# 12V_Buck.net
KiCad netlist of a schematic drawn in Altium Designer
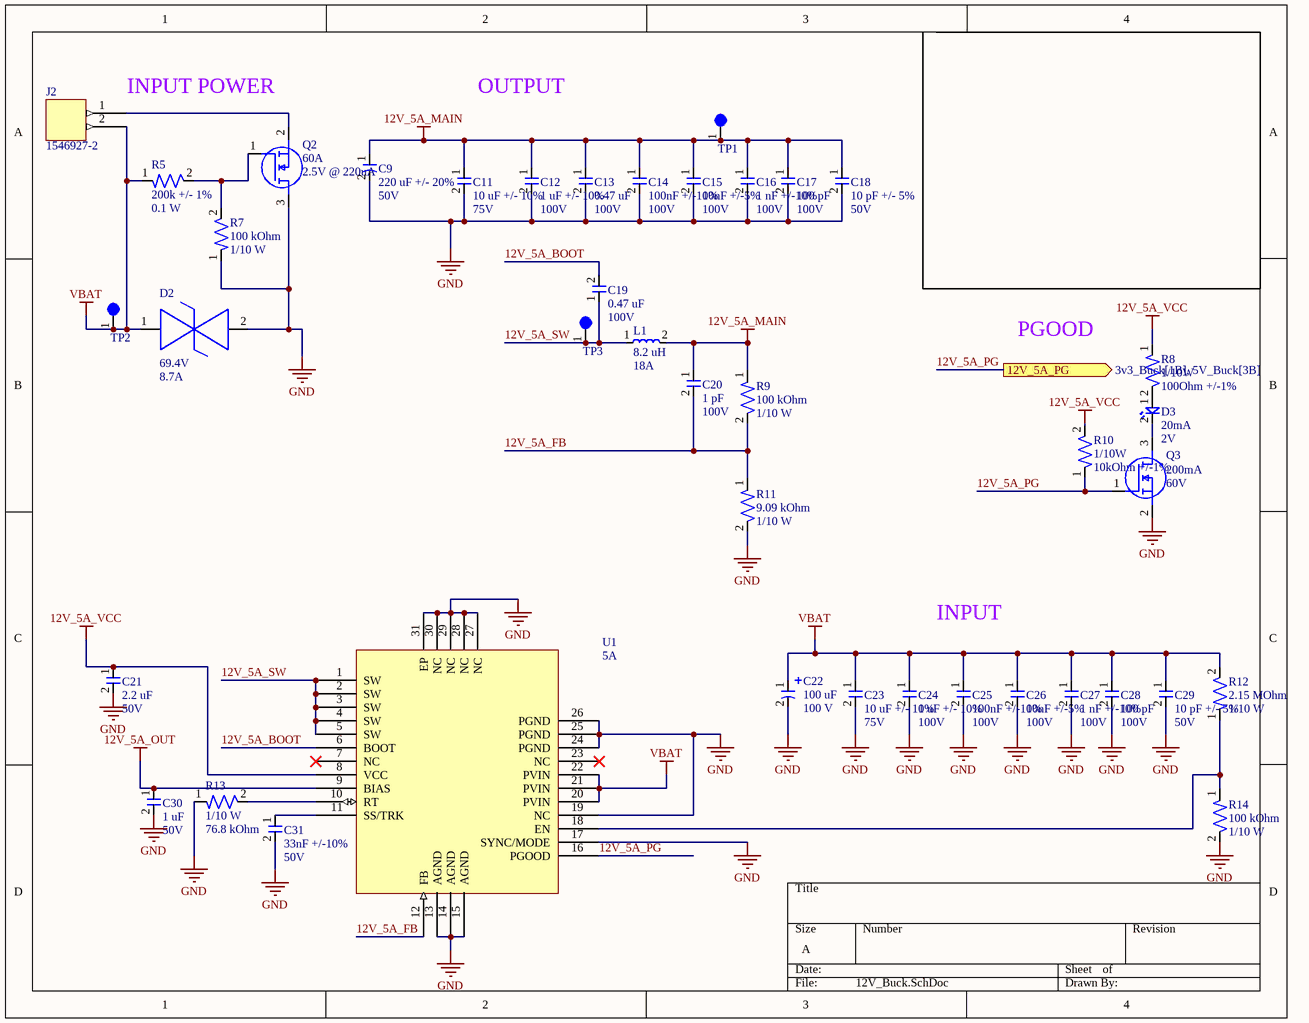
[diagram p0: 12V_Buck.SchDoc]

(export (version "E")
  (design (tool "Eeschema 10.0.6"))
  (components
    (comp (ref "C9")
      (value "50TZV220M10X10.5")
      (footprint "ELEC-220U-0003")
      (description "220 µF 50 V Aluminum Electrolytic Capacitors Radial, Can - SMD 2000 Hrs @ 105°C")
      (fields (field (name "CAPACITANCE") "220 uF +/- 20%") (field (name "VOLTAGE RATING") "50V"))
      (libsource (lib "MasterLib") (part "ELEC-220U-0003"))
    )
    (comp (ref "C11")
      (value "C3225X7R1N106K250AC")
      (footprint "CAP-1210")
      (description "10 µF ±10% 75V Ceramic Capacitor X7R 1210 (3225 Metric)")
      (fields (field (name "CAPACITANCE") "10 uF +/- 10%") (field (name "VOLTAGE RATING") "75V"))
      (libsource (lib "MasterLib") (part "CAP-10U-0004"))
    )
    (comp (ref "C12")
      (value "CL31B105KCHNNNE")
      (footprint "CAP-1206 - duplicate")
      (description "1 µF ±10% 100V Ceramic Capacitor X7R 1206 (3216 Metric)")
      (fields (field (name "CAPACITANCE") "1 uF +/- 10%") (field (name "VOLTAGE") "100V"))
      (libsource (lib "MasterLib") (part "CAP-1U-0001"))
    )
    (comp (ref "C13")
      (value "KAM21KR72A474KL")
      (footprint "CAP-0805")
      (description "0.47 µF ±10% 100V Ceramic Capacitor X7R 0805 (2012 Metric)")
      (fields
        (field (name "TOLERANCE") "+/- 10%")
        (field (name "CAPACITANCE") "0.47 uF")
        (field (name "VOLTAGE") "100V")
      )
      (libsource (lib "MasterLib") (part "CAP-0.47U-0001"))
    )
    (comp (ref "C14")
      (value "CC0603KRX7R0BB104")
      (footprint "CAP-0603")
      (description "CAP CER 0.1UF 100V X7R 0603")
      (fields
        (field (name "MANUFACTURER") "YAGEO")
        (field (name "CAPACITANCE") "100nF +/-10%")
        (field (name "VOLTAGE RATING") "100V")
      )
      (libsource (lib "MasterLib") (part "CAP-100N-0001"))
    )
    (comp (ref "C15")
      (value "C1608C0G2A103J080AC")
      (footprint "CAP-0603")
      (description "CAP CER 10000PF 100V C0G 0603")
      (fields
        (field (name "MANUFACTURER") "TDK Corporation")
        (field (name "CAPACITANCE") "10nF +/-5%")
        (field (name "VOLTAGE RATING") "100V")
      )
      (libsource (lib "MasterLib") (part "CAP-10N-0002"))
    )
    (comp (ref "C16")
      (value "C0603Y102K1RAC7867")
      (footprint "CAP-0603")
      (description "1000 pF ±10% 100V Ceramic Capacitor X7R 0603 (1608 Metric)")
      (fields (field (name "CAPACITANCE") "1 nF +/-10%") (field (name "VOLTAGE") "100V"))
      (libsource (lib "MasterLib") (part "CAP-1N-0001"))
    )
    (comp (ref "C17")
      (value "0603N101J101CT")
      (footprint "CAP-0603")
      (description "100 pF ±5% 100V Ceramic Capacitor C0G, NP0 0603 (1608 Metric)")
      (fields
        (field (name "TOLERANCE") "+/-5%")
        (field (name "CAPACITANCE") "100 pF")
        (field (name "VOLTAGE") "100V")
      )
      (libsource (lib "MasterLib") (part "CAP-100P-0002"))
    )
    (comp (ref "C18")
      (value "0603N100J500CT")
      (footprint "CAP-0603")
      (description "10 pF ±5% 50V Ceramic Capacitor C0G, NP0 0603 (1608 Metric)")
      (fields
        (field (name "MANUFACTURER") "Walshin Technology Corporation")
        (field (name "CAPACITANCE") "10 pF +/- 5%")
        (field (name "VOLTAGE RATING") "50V")
      )
      (libsource (lib "MasterLib") (part "CAP-10P-0001"))
    )
    (comp (ref "C19")
      (value "KAM21KR72A474KL")
      (footprint "CAP-0805")
      (description "0.47 µF ±10% 100V Ceramic Capacitor X7R 0805 (2012 Metric)")
      (fields
        (field (name "TOLERANCE") "+/- 10%")
        (field (name "CAPACITANCE") "0.47 uF")
        (field (name "VOLTAGE") "100V")
      )
      (libsource (lib "MasterLib") (part "CAP-0.47U-0001"))
    )
    (comp (ref "C20")
      (value "885012006087")
      (footprint "CAP-0603")
      (description "1 pF ±0.25pF 100V Ceramic Capacitor C0G, NP0 0603 (1608 Metric)")
      (fields
        (field (name "TOLERANCE") "+/- 0.25 pF")
        (field (name "CAPACITANCE") "1 pF")
        (field (name "VOLTAGE") "100V")
      )
      (libsource (lib "MasterLib") (part "CAP-1P-0001"))
    )
    (comp (ref "C21")
      (value "UMK107BBJ225KA-T")
      (footprint "CAP-0603")
      (description "2.2 µF ±10% 50V Ceramic Capacitor X5R 0603 (1608 Metric)")
      (fields (field (name "CAPACITANCE") "2.2 uF") (field (name "OLTAGE") "50V"))
      (libsource (lib "MasterLib") (part "CAP-2.2U-0001"))
    )
    (comp (ref "C22")
      (value "100SEV100M12.5X16")
      (footprint "ELEC-100U-0001")
      (description "100 µF 100 V Aluminum Electrolytic Capacitors Radial, Can - SMD 2000 Hrs @ 85°C")
      (fields
        (field (name "MANUFACTURER") "Rubycon")
        (field (name "TOLERANCE") "+/- 20%")
        (field (name "CAPACITANCE") "100 uF")
        (field (name "VOLTAGE") "100 V")
      )
      (libsource (lib "MasterLib") (part "ELEC-100U-0001"))
    )
    (comp (ref "C23")
      (value "C3225X7R1N106K250AC")
      (footprint "CAP-1210")
      (description "10 µF ±10% 75V Ceramic Capacitor X7R 1210 (3225 Metric)")
      (fields (field (name "CAPACITANCE") "10 uF +/- 10%") (field (name "VOLTAGE RATING") "75V"))
      (libsource (lib "MasterLib") (part "CAP-10U-0004"))
    )
    (comp (ref "C24")
      (value "CL31B105KCHNNNE")
      (footprint "CAP-1206 - duplicate")
      (description "1 µF ±10% 100V Ceramic Capacitor X7R 1206 (3216 Metric)")
      (fields (field (name "CAPACITANCE") "1 uF +/- 10%") (field (name "VOLTAGE") "100V"))
      (libsource (lib "MasterLib") (part "CAP-1U-0001"))
    )
    (comp (ref "C25")
      (value "CC0603KRX7R0BB104")
      (footprint "CAP-0603")
      (description "CAP CER 0.1UF 100V X7R 0603")
      (fields
        (field (name "MANUFACTURER") "YAGEO")
        (field (name "CAPACITANCE") "100nF +/-10%")
        (field (name "VOLTAGE RATING") "100V")
      )
      (libsource (lib "MasterLib") (part "CAP-100N-0001"))
    )
    (comp (ref "C26")
      (value "C1608C0G2A103J080AC")
      (footprint "CAP-0603")
      (description "CAP CER 10000PF 100V C0G 0603")
      (fields
        (field (name "MANUFACTURER") "TDK Corporation")
        (field (name "CAPACITANCE") "10nF +/-5%")
        (field (name "VOLTAGE RATING") "100V")
      )
      (libsource (lib "MasterLib") (part "CAP-10N-0002"))
    )
    (comp (ref "C27")
      (value "C0603Y102K1RAC7867")
      (footprint "CAP-0603")
      (description "1000 pF ±10% 100V Ceramic Capacitor X7R 0603 (1608 Metric)")
      (fields (field (name "CAPACITANCE") "1 nF +/-10%") (field (name "VOLTAGE") "100V"))
      (libsource (lib "MasterLib") (part "CAP-1N-0001"))
    )
    (comp (ref "C28")
      (value "0603N101J101CT")
      (footprint "CAP-0603")
      (description "100 pF ±5% 100V Ceramic Capacitor C0G, NP0 0603 (1608 Metric)")
      (fields
        (field (name "TOLERANCE") "+/-5%")
        (field (name "CAPACITANCE") "100 pF")
        (field (name "VOLTAGE") "100V")
      )
      (libsource (lib "MasterLib") (part "CAP-100P-0002"))
    )
    (comp (ref "C29")
      (value "0603N100J500CT")
      (footprint "CAP-0603")
      (description "10 pF ±5% 50V Ceramic Capacitor C0G, NP0 0603 (1608 Metric)")
      (fields
        (field (name "MANUFACTURER") "Walshin Technology Corporation")
        (field (name "CAPACITANCE") "10 pF +/- 5%")
        (field (name "VOLTAGE RATING") "50V")
      )
      (libsource (lib "MasterLib") (part "CAP-10P-0001"))
    )
    (comp (ref "C30")
      (value "UMK107AB7105KA-T")
      (footprint "CAP-0603")
      (description "1 µF ±10% 50V Ceramic Capacitor X7R 0603 (1608 Metric)")
      (fields (field (name "CAPACITANCE") "1 uF") (field (name "VOLTAGE") "50V"))
      (libsource (lib "MasterLib") (part "CAP-1U-0002"))
    )
    (comp (ref "C31")
      (value "CC0603KRX7R9BB333")
      (footprint "CAP-0603")
      (description "0.033 µF ±10% 50V Ceramic Capacitor X7R 0603 (1608 Metric)")
      (fields
        (field (name "MANUFACTURER") "YAGEO")
        (field (name "CAPACITANCE") "33nF +/-10%")
        (field (name "VOLTAGE RATING") "50V")
      )
      (libsource (lib "MasterLib") (part "CAP-33N-0001"))
    )
    (comp (ref "D2")
      (value "SMBJE43CAH")
      (footprint "DO-214AA (SMBJ)")
      (description "69.4V Clamp 8.7A Ipp Tvs Diode Surface Mount DO-214AA (SMBJ)")
      (fields (field (name "VCLAMP") "69.4V") (field (name "PEAK PULSER CURRENT") "8.7A"))
      (libsource (lib "MasterLib") (part "DIO-69.4V-0001"))
    )
    (comp (ref "D3")
      (value "150060AS75000")
      (footprint "LED-0603")
      (description "CAP CER 0.1UF 100V X7R 0603")
      (fields
        (field (name "MANUFACTURER") "Wurth Electronik")
        (field (name "CURRENT RATING") "20mA")
        (field (name "VF") "2V")
      )
      (libsource (lib "MasterLib") (part "LED_Amber_0001"))
    )
    (comp (ref "J2")
      (value "1546927-2")
      (footprint "CONN-1546927-2")
      (libsource (lib "MasterLib") (part "CON-2POS-0003"))
    )
    (comp (ref "L1")
      (value "IHLP6767GZER8R2M01")
      (footprint "PWRIND-8.2U-0002")
      (description "8.2 µH Shielded Molded Inductor 18 A 10.66mOhm Max Nonstandard")
      (fields
        (field (name "TOLERANCE") "+/-20%")
        (field (name "INDUCTANCE") "8.2 uH")
        (field (name "DCI") "18A")
      )
      (libsource (lib "MasterLib") (part "PWRIND-8.2U-0002"))
    )
    (comp (ref "Q2")
      (value "TPH7R006PL,L1Q")
      (footprint "NMOS-8PowerVDFN")
      (description "N-Channel 60 V 60A (Tc) 81W (Tc) Surface Mount 8-SOP Advance (5x5)")
      (fields (field (name "DRAIN CURRENT") "60A") (field (name "VGS") "2.5V @ 220uA"))
      (libsource (lib "MasterLib") (part "NMOS-60A-0001"))
    )
    (comp (ref "Q3")
      (value "T2N7002AK,LM")
      (footprint "NMOS-SOT23-3")
      (description "MOSFET N-CH 60V 200MA SOT23")
      (fields
        (field (name "MANUFACTURER") "Toshiba")
        (field (name "ID-CONTINUOUS") "200mA")
        (field (name "VDS-MAX") "60V")
      )
      (libsource (lib "MasterLib") (part "NMOS-200MA-0001"))
    )
    (comp (ref "R5")
      (value "ERJ-3EKF2003V")
      (footprint "RES-0603")
      (description "200 kOhms ±1% 0.1W, 1/10W Chip Resistor 0603 (1608 Metric) Automotive AEC-Q200 Thick Film")
      (fields
        (field (name "MANUFACTURER") "Panasonic Electronic Components")
        (field (name "RESISTANCE") "200k +/- 1%")
        (field (name "POWER RATING") "0.1 W")
      )
      (libsource (lib "MasterLib") (part "RES-200K-0001"))
    )
    (comp (ref "R7")
      (value "RC0603FR-07100KL")
      (footprint "RES-0603")
      (description "100 kOhms ±1% 0.1W, 1/10W Chip Resistor 0603 (1608 Metric) Moisture Resistant Thick Film")
      (fields
        (field (name "TOLERANCE") "+/- 1%")
        (field (name "RESISTANCE") "100 kOhm")
        (field (name "POWER") "1/10 W")
      )
      (libsource (lib "MasterLib") (part "RES-100K-0003"))
    )
    (comp (ref "R8")
      (value "AC0603FR-10100RL")
      (footprint "RES-0603")
      (description "100 Ohms ±1% 0.1W, 1/10W Chip Resistor 0603 (1608 Metric) Automotive AEC-Q200 Thick Film")
      (fields
        (field (name "MANUFACTURER") "YAGEO")
        (field (name "POWER RATING") "1/10W")
        (field (name "RESISTANCE") "100Ohm +/-1%")
      )
      (libsource (lib "MasterLib") (part "RES-100-0002"))
    )
    (comp (ref "R9")
      (value "RC0603FR-07100KL")
      (footprint "RES-0603")
      (description "100 kOhms ±1% 0.1W, 1/10W Chip Resistor 0603 (1608 Metric) Moisture Resistant Thick Film")
      (fields
        (field (name "TOLERANCE") "+/- 1%")
        (field (name "RESISTANCE") "100 kOhm")
        (field (name "POWER") "1/10 W")
      )
      (libsource (lib "MasterLib") (part "RES-100K-0003"))
    )
    (comp (ref "R10")
      (value "RC0603FR-0710KP")
      (footprint "RES-0603")
      (description "RES SMD 10K OHM 1% 1/10W 0603")
      (fields
        (field (name "MANUFACTURER") "YAGEO")
        (field (name "POWER RATING") "1/10W")
        (field (name "RESISTANCE") "10kOhm +/-1%")
      )
      (libsource (lib "MasterLib") (part "RES-10K-0002"))
    )
    (comp (ref "R11")
      (value "RC0603FR-079K09L")
      (footprint "RES-0603")
      (description "9.09 kOhms ±1% 0.1W, 1/10W Chip Resistor 0603 (1608 Metric) Moisture Resistant Thick Film")
      (fields
        (field (name "TOLERANCE") "+/-1%")
        (field (name "RESISTANCE") "9.09 kOhm")
        (field (name "POWER") "1/10 W")
      )
      (libsource (lib "MasterLib") (part "RES-9.09K-0001"))
    )
    (comp (ref "R12")
      (value "RC0603FR-072M15L")
      (footprint "RES-0603")
      (description "2.15 MOhms ±1% 0.1W, 1/10W Chip Resistor 0603 (1608 Metric) Moisture Resistant Thick Film")
      (fields
        (field (name "TOLERANCE") "+/-1%")
        (field (name "RESISTANCE") "2.15 MOhm")
        (field (name "POWER") "1/10 W")
      )
      (libsource (lib "MasterLib") (part "RES-2.15M-0001"))
    )
    (comp (ref "R13")
      (value "RC0603FR-0776K8L")
      (footprint "RES-0603")
      (description "76.8 kOhms ±1% 0.1W, 1/10W Chip Resistor 0603 (1608 Metric) Moisture Resistant Thick Film")
      (fields
        (field (name "MANUFACTURER") "Yageo")
        (field (name "TOLERANCE") "+/- 1%")
        (field (name "POWER") "1/10 W")
        (field (name "RESISTANCE") "76.8 kOhm")
      )
      (libsource (lib "MasterLib") (part "RES-76.8K-0001"))
    )
    (comp (ref "R14")
      (value "RC0603FR-07100KL")
      (footprint "RES-0603")
      (description "100 kOhms ±1% 0.1W, 1/10W Chip Resistor 0603 (1608 Metric) Moisture Resistant Thick Film")
      (fields
        (field (name "TOLERANCE") "+/- 1%")
        (field (name "RESISTANCE") "100 kOhm")
        (field (name "POWER") "1/10 W")
      )
      (libsource (lib "MasterLib") (part "RES-100K-0003"))
    )
    (comp (ref "TP1")
      (value "5003")
      (footprint "TEST-POINT-0001")
      (description "Oranange PC Test Point, Miniature Phoisphor Bronze Silver Plating Through Hole Mounting Type")
      (libsource (lib "MasterLib") (part "TEST-POINT-0001"))
    )
    (comp (ref "TP2")
      (value "5003")
      (footprint "TEST-POINT-0001")
      (description "Oranange PC Test Point, Miniature Phoisphor Bronze Silver Plating Through Hole Mounting Type")
      (libsource (lib "MasterLib") (part "TEST-POINT-0001"))
    )
    (comp (ref "TP3")
      (value "5003")
      (footprint "TEST-POINT-0001")
      (description "Oranange PC Test Point, Miniature Phoisphor Bronze Silver Plating Through Hole Mounting Type")
      (libsource (lib "MasterLib") (part "TEST-POINT-0001"))
    )
    (comp (ref "U1")
      (value "LM76005RNPR")
      (footprint "IC-30-WQFN(6x4)")
      (description "Buck Switching Regulator IC Positive Adjustable 1V 1 Output 5A 30-WFQFN Exposed Pad")
      (fields (field (name "MANUFACTURER") "Texas Instruments") (field (name "CURRENT") "5A"))
      (libsource (lib "MasterLib") (part "IC-BUCK-0006"))
    )
  )
  (nets
    (net (code "1") (name "/12V_5A_BOOT") (class "Default")
      (node (ref "C19") (pin "2") (pinfunction "2_2") (pintype "passive"))
      (node (ref "U1") (pin "6") (pinfunction "BOOT_6") (pintype "power_in"))
    )
    (net (code "2") (name "/12V_5A_FB") (class "Default")
      (node (ref "C20") (pin "2") (pinfunction "2_2") (pintype "passive"))
      (node (ref "R11") (pin "1") (pinfunction "1_1") (pintype "passive"))
      (node (ref "R9") (pin "2") (pinfunction "2_2") (pintype "passive"))
      (node (ref "U1") (pin "12") (pinfunction "FB_12") (pintype "input"))
    )
    (net (code "3") (name "/12V_5A_PG") (class "Default")
      (node (ref "Q3") (pin "1") (pinfunction "G_1") (pintype "passive"))
      (node (ref "R10") (pin "1") (pinfunction "1_1") (pintype "passive"))
      (node (ref "U1") (pin "16") (pinfunction "PGOOD_16") (pintype "power_in"))
    )
    (net (code "4") (name "/12V_5A_SW") (class "Default")
      (node (ref "C19") (pin "1") (pinfunction "1_1") (pintype "passive"))
      (node (ref "L1") (pin "1") (pinfunction "1_1") (pintype "passive"))
      (node (ref "TP3") (pin "1") (pinfunction "0_1") (pintype "passive"))
      (node (ref "U1") (pin "1") (pinfunction "SW_1") (pintype "power_in"))
      (node (ref "U1") (pin "2") (pinfunction "SW_2") (pintype "power_in"))
      (node (ref "U1") (pin "3") (pinfunction "SW_3") (pintype "power_in"))
      (node (ref "U1") (pin "4") (pinfunction "SW_4") (pintype "power_in"))
      (node (ref "U1") (pin "5") (pinfunction "SW_5") (pintype "power_in"))
    )
    (net (code "5") (name "12V_5A_MAIN") (class "Default")
      (node (ref "C11") (pin "1") (pinfunction "1_1") (pintype "passive"))
      (node (ref "C12") (pin "1") (pinfunction "1_1") (pintype "passive"))
      (node (ref "C13") (pin "1") (pinfunction "1_1") (pintype "passive"))
      (node (ref "C14") (pin "1") (pinfunction "1_1") (pintype "passive"))
      (node (ref "C15") (pin "1") (pinfunction "1_1") (pintype "passive"))
      (node (ref "C16") (pin "1") (pinfunction "1_1") (pintype "passive"))
      (node (ref "C17") (pin "1") (pinfunction "1_1") (pintype "passive"))
      (node (ref "C18") (pin "1") (pinfunction "1_1") (pintype "passive"))
      (node (ref "C20") (pin "1") (pinfunction "1_1") (pintype "passive"))
      (node (ref "C9") (pin "1") (pinfunction "1_1") (pintype "passive"))
      (node (ref "L1") (pin "2") (pinfunction "2_2") (pintype "passive"))
      (node (ref "R9") (pin "1") (pinfunction "1_1") (pintype "passive"))
      (node (ref "TP1") (pin "1") (pinfunction "0_1") (pintype "passive"))
    )
    (net (code "6") (name "12V_5A_OUT") (class "Default")
      (node (ref "C30") (pin "1") (pinfunction "1_1") (pintype "passive"))
      (node (ref "U1") (pin "9") (pinfunction "BIAS_9") (pintype "power_in"))
    )
    (net (code "7") (name "12V_5A_VCC") (class "Default")
      (node (ref "C21") (pin "1") (pinfunction "1_1") (pintype "passive"))
      (node (ref "R10") (pin "2") (pinfunction "2_2") (pintype "passive"))
      (node (ref "R8") (pin "1") (pinfunction "1_1") (pintype "passive"))
      (node (ref "U1") (pin "8") (pinfunction "VCC_8") (pintype "power_in"))
    )
    (net (code "8") (name "GND") (class "Default")
      (node (ref "C11") (pin "2") (pinfunction "2_2") (pintype "passive"))
      (node (ref "C12") (pin "2") (pinfunction "2_2") (pintype "passive"))
      (node (ref "C13") (pin "2") (pinfunction "2_2") (pintype "passive"))
      (node (ref "C14") (pin "2") (pinfunction "2_2") (pintype "passive"))
      (node (ref "C15") (pin "2") (pinfunction "2_2") (pintype "passive"))
      (node (ref "C16") (pin "2") (pinfunction "2_2") (pintype "passive"))
      (node (ref "C17") (pin "2") (pinfunction "2_2") (pintype "passive"))
      (node (ref "C18") (pin "2") (pinfunction "2_2") (pintype "passive"))
      (node (ref "C21") (pin "2") (pinfunction "2_2") (pintype "passive"))
      (node (ref "C22") (pin "2") (pinfunction "2_2") (pintype "passive"))
      (node (ref "C23") (pin "2") (pinfunction "2_2") (pintype "passive"))
      (node (ref "C24") (pin "2") (pinfunction "2_2") (pintype "passive"))
      (node (ref "C25") (pin "2") (pinfunction "2_2") (pintype "passive"))
      (node (ref "C26") (pin "2") (pinfunction "2_2") (pintype "passive"))
      (node (ref "C27") (pin "2") (pinfunction "2_2") (pintype "passive"))
      (node (ref "C28") (pin "2") (pinfunction "2_2") (pintype "passive"))
      (node (ref "C29") (pin "2") (pinfunction "2_2") (pintype "passive"))
      (node (ref "C30") (pin "2") (pinfunction "2_2") (pintype "passive"))
      (node (ref "C31") (pin "2") (pinfunction "2_2") (pintype "passive"))
      (node (ref "C9") (pin "2") (pinfunction "2_2") (pintype "passive"))
      (node (ref "D2") (pin "2") (pintype "passive"))
      (node (ref "Q2") (pin "3") (pinfunction "D_3") (pintype "passive"))
      (node (ref "Q3") (pin "2") (pinfunction "S_2") (pintype "passive"))
      (node (ref "R11") (pin "2") (pinfunction "2_2") (pintype "passive"))
      (node (ref "R13") (pin "1") (pinfunction "1_1") (pintype "passive"))
      (node (ref "R14") (pin "2") (pinfunction "2_2") (pintype "passive"))
      (node (ref "R7") (pin "1") (pinfunction "1_1") (pintype "passive"))
      (node (ref "U1") (pin "13") (pinfunction "AGND_13") (pintype "power_in"))
      (node (ref "U1") (pin "14") (pinfunction "AGND_14") (pintype "power_in"))
      (node (ref "U1") (pin "15") (pinfunction "AGND_15") (pintype "power_in"))
      (node (ref "U1") (pin "17") (pinfunction "SYNC/MODE_17") (pintype "power_in"))
      (node (ref "U1") (pin "19") (pinfunction "NC_19") (pintype "power_in"))
      (node (ref "U1") (pin "24") (pinfunction "PGND_24") (pintype "power_in"))
      (node (ref "U1") (pin "25") (pinfunction "PGND_25") (pintype "power_in"))
      (node (ref "U1") (pin "26") (pinfunction "PGND_26") (pintype "power_in"))
      (node (ref "U1") (pin "27") (pinfunction "NC_27") (pintype "power_in"))
      (node (ref "U1") (pin "28") (pinfunction "NC_28") (pintype "power_in"))
      (node (ref "U1") (pin "29") (pinfunction "NC_29") (pintype "power_in"))
      (node (ref "U1") (pin "30") (pinfunction "NC_30") (pintype "power_in"))
      (node (ref "U1") (pin "31") (pinfunction "EP_31") (pintype "power_in"))
    )
    (net (code "9") (name "Net-(D3-Pad1)") (class "Default")
      (node (ref "D3") (pin "1") (pinfunction "1_1") (pintype "passive"))
      (node (ref "R8") (pin "2") (pinfunction "2_2") (pintype "passive"))
    )
    (net (code "10") (name "Net-(Q2-G)") (class "Default")
      (node (ref "Q2") (pin "1") (pinfunction "G_1") (pintype "passive"))
      (node (ref "R5") (pin "2") (pinfunction "2_2") (pintype "passive"))
      (node (ref "R7") (pin "2") (pinfunction "2_2") (pintype "passive"))
    )
    (net (code "11") (name "Net-(Q2-S)") (class "Default")
      (node (ref "J2") (pin "1") (pintype "output"))
      (node (ref "Q2") (pin "2") (pinfunction "S_2") (pintype "passive"))
    )
    (net (code "12") (name "Net-(Q3-D)") (class "Default")
      (node (ref "D3") (pin "2") (pinfunction "2_2") (pintype "passive"))
      (node (ref "Q3") (pin "3") (pinfunction "D_3") (pintype "passive"))
    )
    (net (code "13") (name "Net-(U1-EN)") (class "Default")
      (node (ref "R12") (pin "1") (pinfunction "1_1") (pintype "passive"))
      (node (ref "R14") (pin "1") (pinfunction "1_1") (pintype "passive"))
      (node (ref "U1") (pin "18") (pinfunction "EN_18") (pintype "power_in"))
    )
    (net (code "14") (name "Net-(U1-RT)") (class "Default")
      (node (ref "R13") (pin "2") (pinfunction "2_2") (pintype "passive"))
      (node (ref "U1") (pin "10") (pinfunction "RT_10") (pintype "bidirectional"))
    )
    (net (code "15") (name "Net-(U1-SS{slash}TRK)") (class "Default")
      (node (ref "C31") (pin "1") (pinfunction "1_1") (pintype "passive"))
      (node (ref "U1") (pin "11") (pinfunction "SS/TRK_11") (pintype "passive"))
    )
    (net (code "16") (name "VBAT") (class "Default")
      (node (ref "C22") (pin "1") (pinfunction "1_1") (pintype "passive"))
      (node (ref "C23") (pin "1") (pinfunction "1_1") (pintype "passive"))
      (node (ref "C24") (pin "1") (pinfunction "1_1") (pintype "passive"))
      (node (ref "C25") (pin "1") (pinfunction "1_1") (pintype "passive"))
      (node (ref "C26") (pin "1") (pinfunction "1_1") (pintype "passive"))
      (node (ref "C27") (pin "1") (pinfunction "1_1") (pintype "passive"))
      (node (ref "C28") (pin "1") (pinfunction "1_1") (pintype "passive"))
      (node (ref "C29") (pin "1") (pinfunction "1_1") (pintype "passive"))
      (node (ref "D2") (pin "1") (pintype "passive"))
      (node (ref "J2") (pin "2") (pintype "output"))
      (node (ref "R12") (pin "2") (pinfunction "2_2") (pintype "passive"))
      (node (ref "R5") (pin "1") (pinfunction "1_1") (pintype "passive"))
      (node (ref "TP2") (pin "1") (pinfunction "0_1") (pintype "passive"))
      (node (ref "U1") (pin "20") (pinfunction "PVIN_20") (pintype "power_in"))
      (node (ref "U1") (pin "21") (pinfunction "PVIN_21") (pintype "power_in"))
      (node (ref "U1") (pin "22") (pinfunction "PVIN_22") (pintype "power_in"))
    )
    (net (code "17") (name "unconnected-(U1-NC-Pad7)") (class "Default")
      (node (ref "U1") (pin "7") (pinfunction "NC_7") (pintype "power_in+no_connect"))
    )
    (net (code "18") (name "unconnected-(U1-NC-Pad23)") (class "Default")
      (node (ref "U1") (pin "23") (pinfunction "NC_23") (pintype "tri_state+no_connect"))
    )
  )
)
